# working.net
KiCad netlist of a schematic drawn in EAGLE
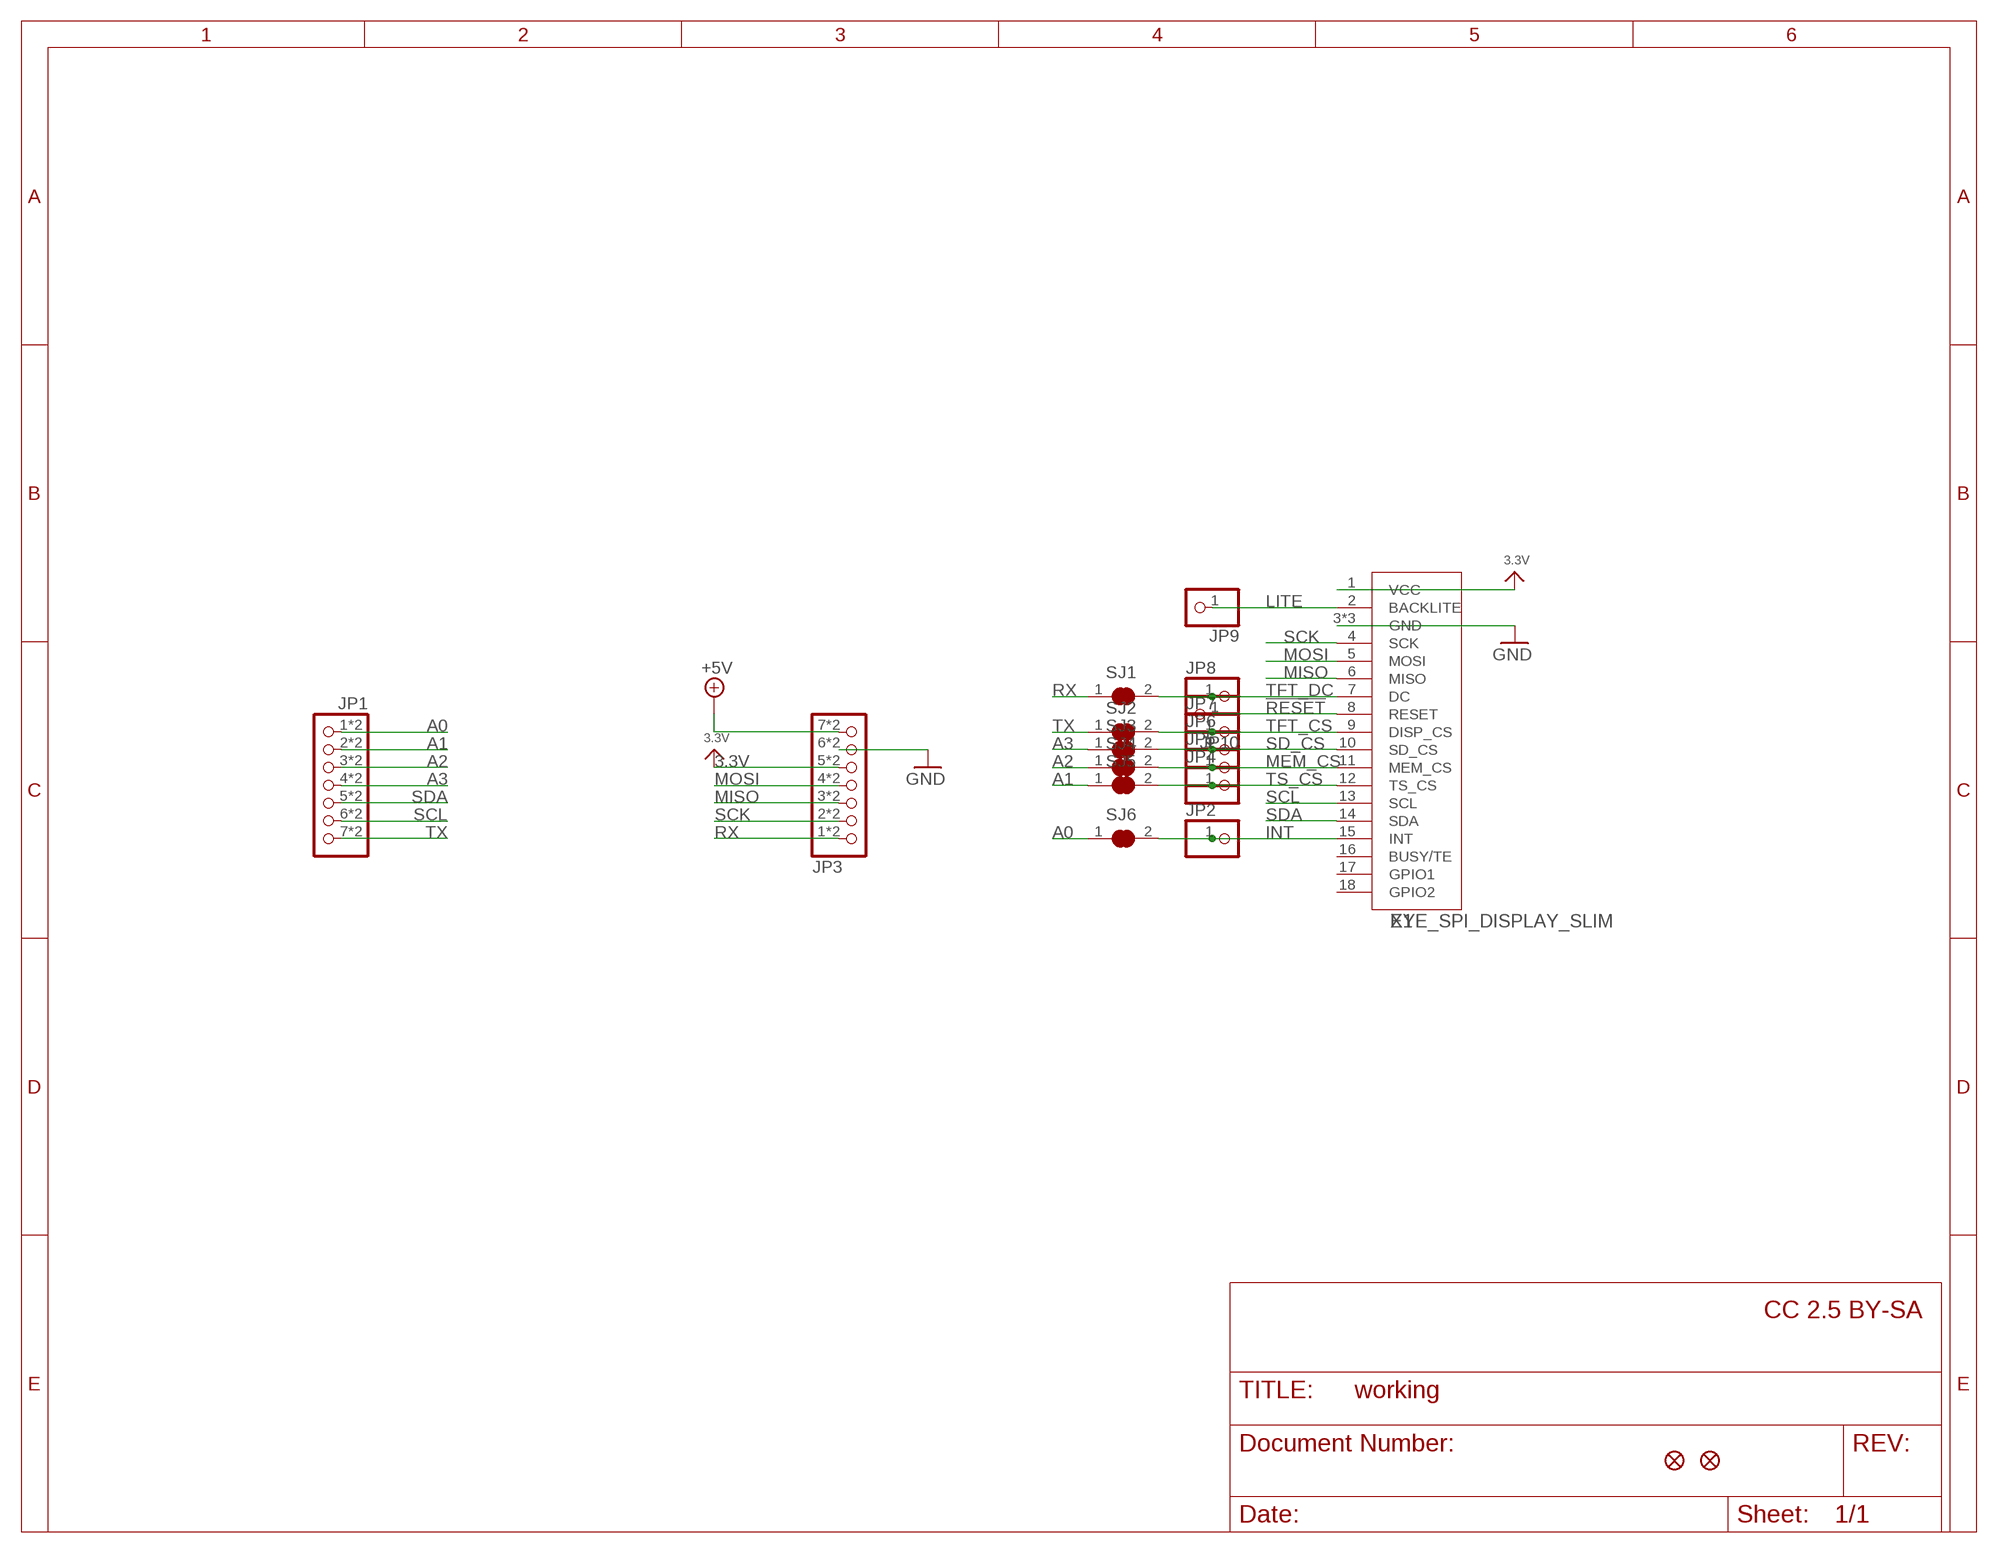
[diagram p0: schematic, sheet 1]

(export (version "E")
  (design (tool "Eeschema 10.0.6"))
  (components
    (comp (ref "JP1")
      (value "HEADER-1X7_CASTEL")
      (footprint "eagle-import:1X07_CASTEL")
      (libsource (lib "eagle-import") (part "HEADER-1X7_CASTEL"))
    )
    (comp (ref "JP2")
      (value "HEADER-1X12MM")
      (footprint "eagle-import:1X01_2MM")
      (libsource (lib "eagle-import") (part "HEADER-1X12MM"))
    )
    (comp (ref "JP3")
      (value "HEADER-1X7_CASTEL")
      (footprint "eagle-import:1X07_CASTEL")
      (libsource (lib "eagle-import") (part "HEADER-1X7_CASTEL"))
    )
    (comp (ref "JP4")
      (value "HEADER-1X12MM")
      (footprint "eagle-import:1X01_2MM")
      (libsource (lib "eagle-import") (part "HEADER-1X12MM"))
    )
    (comp (ref "JP5")
      (value "HEADER-1X12MM")
      (footprint "eagle-import:1X01_2MM")
      (libsource (lib "eagle-import") (part "HEADER-1X12MM"))
    )
    (comp (ref "JP6")
      (value "HEADER-1X12MM")
      (footprint "eagle-import:1X01_2MM")
      (libsource (lib "eagle-import") (part "HEADER-1X12MM"))
    )
    (comp (ref "JP7")
      (value "HEADER-1X12MM")
      (footprint "eagle-import:1X01_2MM")
      (libsource (lib "eagle-import") (part "HEADER-1X12MM"))
    )
    (comp (ref "JP8")
      (value "HEADER-1X12MM")
      (footprint "eagle-import:1X01_2MM")
      (libsource (lib "eagle-import") (part "HEADER-1X12MM"))
    )
    (comp (ref "JP9")
      (value "HEADER-1X12MM")
      (footprint "eagle-import:1X01_2MM")
      (libsource (lib "eagle-import") (part "HEADER-1X12MM"))
    )
    (comp (ref "JP10")
      (value "HEADER-1X12MM")
      (footprint "eagle-import:1X01_2MM")
      (libsource (lib "eagle-import") (part "HEADER-1X12MM"))
    )
    (comp (ref "SJ1")
      (value "SOLDERJUMPER_CLOSED")
      (footprint "eagle-import:SOLDERJUMPER_CLOSEDWIRE")
      (libsource (lib "eagle-import") (part "SOLDERJUMPER_CLOSED"))
    )
    (comp (ref "SJ2")
      (value "SOLDERJUMPER_CLOSED")
      (footprint "eagle-import:SOLDERJUMPER_CLOSEDWIRE")
      (libsource (lib "eagle-import") (part "SOLDERJUMPER_CLOSED"))
    )
    (comp (ref "SJ3")
      (value "SOLDERJUMPER_CLOSED")
      (footprint "eagle-import:SOLDERJUMPER_CLOSEDWIRE")
      (libsource (lib "eagle-import") (part "SOLDERJUMPER_CLOSED"))
    )
    (comp (ref "SJ4")
      (value "SOLDERJUMPER_CLOSED")
      (footprint "eagle-import:SOLDERJUMPER_CLOSEDWIRE")
      (libsource (lib "eagle-import") (part "SOLDERJUMPER_CLOSED"))
    )
    (comp (ref "SJ5")
      (value "SOLDERJUMPER_CLOSED")
      (footprint "eagle-import:SOLDERJUMPER_CLOSEDWIRE")
      (libsource (lib "eagle-import") (part "SOLDERJUMPER_CLOSED"))
    )
    (comp (ref "SJ6")
      (value "SOLDERJUMPER_CLOSED")
      (footprint "eagle-import:SOLDERJUMPER_CLOSEDWIRE")
      (libsource (lib "eagle-import") (part "SOLDERJUMPER_CLOSED"))
    )
    (comp (ref "U$6")
      (value "FIDUCIAL_1MM")
      (footprint "eagle-import:FIDUCIAL_1MM")
      (libsource (lib "eagle-import") (part "FIDUCIAL_1MM"))
    )
    (comp (ref "U$8")
      (value "FIDUCIAL_1MM")
      (footprint "eagle-import:FIDUCIAL_1MM")
      (libsource (lib "eagle-import") (part "FIDUCIAL_1MM"))
    )
    (comp (ref "X1")
      (value "EYE_SPI_DISPLAY_SLIM")
      (footprint "eagle-import:EYE_SPI_DISPLAY_SLIM")
      (libsource (lib "eagle-import") (part "EYE_SPI_DISPLAY_SLIM"))
    )
  )
  (nets
    (net (code "1") (name "+5V") (class "Default")
      (node (ref "JP3") (pin "7") (pinfunction "7_7") (pintype "passive"))
      (node (ref "JP3") (pin "7C") (pinfunction "7_7C") (pintype "passive"))
    )
    (net (code "2") (name "/A0") (class "Default")
      (node (ref "JP1") (pin "1") (pinfunction "1_1") (pintype "passive"))
      (node (ref "JP1") (pin "1C") (pinfunction "1_1C") (pintype "passive"))
      (node (ref "SJ6") (pin "1") (pinfunction "1_1") (pintype "passive"))
    )
    (net (code "3") (name "/A1") (class "Default")
      (node (ref "JP1") (pin "2") (pinfunction "2_2") (pintype "passive"))
      (node (ref "JP1") (pin "2C") (pinfunction "2_2C") (pintype "passive"))
      (node (ref "SJ5") (pin "1") (pinfunction "1_1") (pintype "passive"))
    )
    (net (code "4") (name "/A2") (class "Default")
      (node (ref "JP1") (pin "3") (pinfunction "3_3") (pintype "passive"))
      (node (ref "JP1") (pin "3C") (pinfunction "3_3C") (pintype "passive"))
      (node (ref "SJ4") (pin "1") (pinfunction "1_1") (pintype "passive"))
    )
    (net (code "5") (name "/A3") (class "Default")
      (node (ref "JP1") (pin "4") (pinfunction "4_4") (pintype "passive"))
      (node (ref "JP1") (pin "4C") (pinfunction "4_4C") (pintype "passive"))
      (node (ref "SJ3") (pin "1") (pinfunction "1_1") (pintype "passive"))
    )
    (net (code "6") (name "/INT") (class "Default")
      (node (ref "JP2") (pin "1") (pinfunction "1_1") (pintype "passive"))
      (node (ref "SJ6") (pin "2") (pinfunction "2_2") (pintype "passive"))
      (node (ref "X1") (pin "15") (pinfunction "INT_15") (pintype "output"))
    )
    (net (code "7") (name "/LITE") (class "Default")
      (node (ref "JP9") (pin "1") (pinfunction "1_1") (pintype "passive"))
      (node (ref "X1") (pin "2") (pinfunction "BACKLITE_2") (pintype "input"))
    )
    (net (code "8") (name "/MEM_CS") (class "Default")
      (node (ref "JP5") (pin "1") (pinfunction "1_1") (pintype "passive"))
      (node (ref "SJ4") (pin "2") (pinfunction "2_2") (pintype "passive"))
      (node (ref "X1") (pin "11") (pinfunction "MEM_CS_11") (pintype "input"))
    )
    (net (code "9") (name "/MISO") (class "Default")
      (node (ref "JP3") (pin "3") (pinfunction "3_3") (pintype "passive"))
      (node (ref "JP3") (pin "3C") (pinfunction "3_3C") (pintype "passive"))
      (node (ref "X1") (pin "6") (pinfunction "MISO_6") (pintype "output"))
    )
    (net (code "10") (name "/MOSI") (class "Default")
      (node (ref "JP3") (pin "4") (pinfunction "4_4") (pintype "passive"))
      (node (ref "JP3") (pin "4C") (pinfunction "4_4C") (pintype "passive"))
      (node (ref "X1") (pin "5") (pinfunction "MOSI_5") (pintype "input"))
    )
    (net (code "11") (name "/RX") (class "Default")
      (node (ref "JP3") (pin "1") (pinfunction "1_1") (pintype "passive"))
      (node (ref "JP3") (pin "1C") (pinfunction "1_1C") (pintype "passive"))
      (node (ref "SJ1") (pin "1") (pinfunction "1_1") (pintype "passive"))
    )
    (net (code "12") (name "/SCK") (class "Default")
      (node (ref "JP3") (pin "2") (pinfunction "2_2") (pintype "passive"))
      (node (ref "JP3") (pin "2C") (pinfunction "2_2C") (pintype "passive"))
      (node (ref "X1") (pin "4") (pinfunction "SCK_4") (pintype "input"))
    )
    (net (code "13") (name "/SCL") (class "Default")
      (node (ref "JP1") (pin "6") (pinfunction "6_6") (pintype "passive"))
      (node (ref "JP1") (pin "6C") (pinfunction "6_6C") (pintype "passive"))
      (node (ref "X1") (pin "13") (pinfunction "SCL_13") (pintype "input"))
    )
    (net (code "14") (name "/SDA") (class "Default")
      (node (ref "JP1") (pin "5") (pinfunction "5_5") (pintype "passive"))
      (node (ref "JP1") (pin "5C") (pinfunction "5_5C") (pintype "passive"))
      (node (ref "X1") (pin "14") (pinfunction "SDA_14") (pintype "bidirectional"))
    )
    (net (code "15") (name "/SD_CS") (class "Default")
      (node (ref "JP6") (pin "1") (pinfunction "1_1") (pintype "passive"))
      (node (ref "SJ3") (pin "2") (pinfunction "2_2") (pintype "passive"))
      (node (ref "X1") (pin "10") (pinfunction "SD_CS_10") (pintype "input"))
    )
    (net (code "16") (name "/TFT_CS") (class "Default")
      (node (ref "JP7") (pin "1") (pinfunction "1_1") (pintype "passive"))
      (node (ref "SJ2") (pin "2") (pinfunction "2_2") (pintype "passive"))
      (node (ref "X1") (pin "9") (pinfunction "DISP_CS_9") (pintype "input"))
    )
    (net (code "17") (name "/TFT_DC") (class "Default")
      (node (ref "JP8") (pin "1") (pinfunction "1_1") (pintype "passive"))
      (node (ref "SJ1") (pin "2") (pinfunction "2_2") (pintype "passive"))
      (node (ref "X1") (pin "7") (pinfunction "DC_7") (pintype "input"))
    )
    (net (code "18") (name "/TS_CS") (class "Default")
      (node (ref "JP4") (pin "1") (pinfunction "1_1") (pintype "passive"))
      (node (ref "SJ5") (pin "2") (pinfunction "2_2") (pintype "passive"))
      (node (ref "X1") (pin "12") (pinfunction "TS_CS_12") (pintype "input"))
    )
    (net (code "19") (name "/TX") (class "Default")
      (node (ref "JP1") (pin "7") (pinfunction "7_7") (pintype "passive"))
      (node (ref "JP1") (pin "7C") (pinfunction "7_7C") (pintype "passive"))
      (node (ref "SJ2") (pin "1") (pinfunction "1_1") (pintype "passive"))
    )
    (net (code "20") (name "/~{RESET}") (class "Default")
      (node (ref "JP10") (pin "1") (pinfunction "1_1") (pintype "passive"))
      (node (ref "X1") (pin "8") (pinfunction "RESET_8") (pintype "input"))
    )
    (net (code "21") (name "3.3V") (class "Default")
      (node (ref "JP3") (pin "5") (pinfunction "5_5") (pintype "passive"))
      (node (ref "JP3") (pin "5C") (pinfunction "5_5C") (pintype "passive"))
      (node (ref "X1") (pin "1") (pinfunction "VCC_1") (pintype "power_in"))
    )
    (net (code "22") (name "GND") (class "Default")
      (node (ref "JP3") (pin "6") (pinfunction "6_6") (pintype "passive"))
      (node (ref "JP3") (pin "6C") (pinfunction "6_6C") (pintype "passive"))
      (node (ref "X1") (pin "3") (pinfunction "GND_3") (pintype "power_in"))
      (node (ref "X1") (pin "SUPPORT1") (pinfunction "GND_SUPPORT1") (pintype "power_in"))
      (node (ref "X1") (pin "SUPPORT2") (pinfunction "GND_SUPPORT2") (pintype "power_in"))
    )
    (net (code "23") (name "unconnected-(X1-BUSY{slash}TE-Pad16)") (class "Default")
      (node (ref "X1") (pin "16") (pinfunction "BUSY/TE_16") (pintype "output"))
    )
    (net (code "24") (name "unconnected-(X1-GPIO1-Pad17)") (class "Default")
      (node (ref "X1") (pin "17") (pinfunction "GPIO1_17") (pintype "passive"))
    )
    (net (code "25") (name "unconnected-(X1-GPIO2-Pad18)") (class "Default")
      (node (ref "X1") (pin "18") (pinfunction "GPIO2_18") (pintype "passive"))
    )
  )
)
